# Connectors.net
KiCad netlist of a schematic drawn in Altium Designer
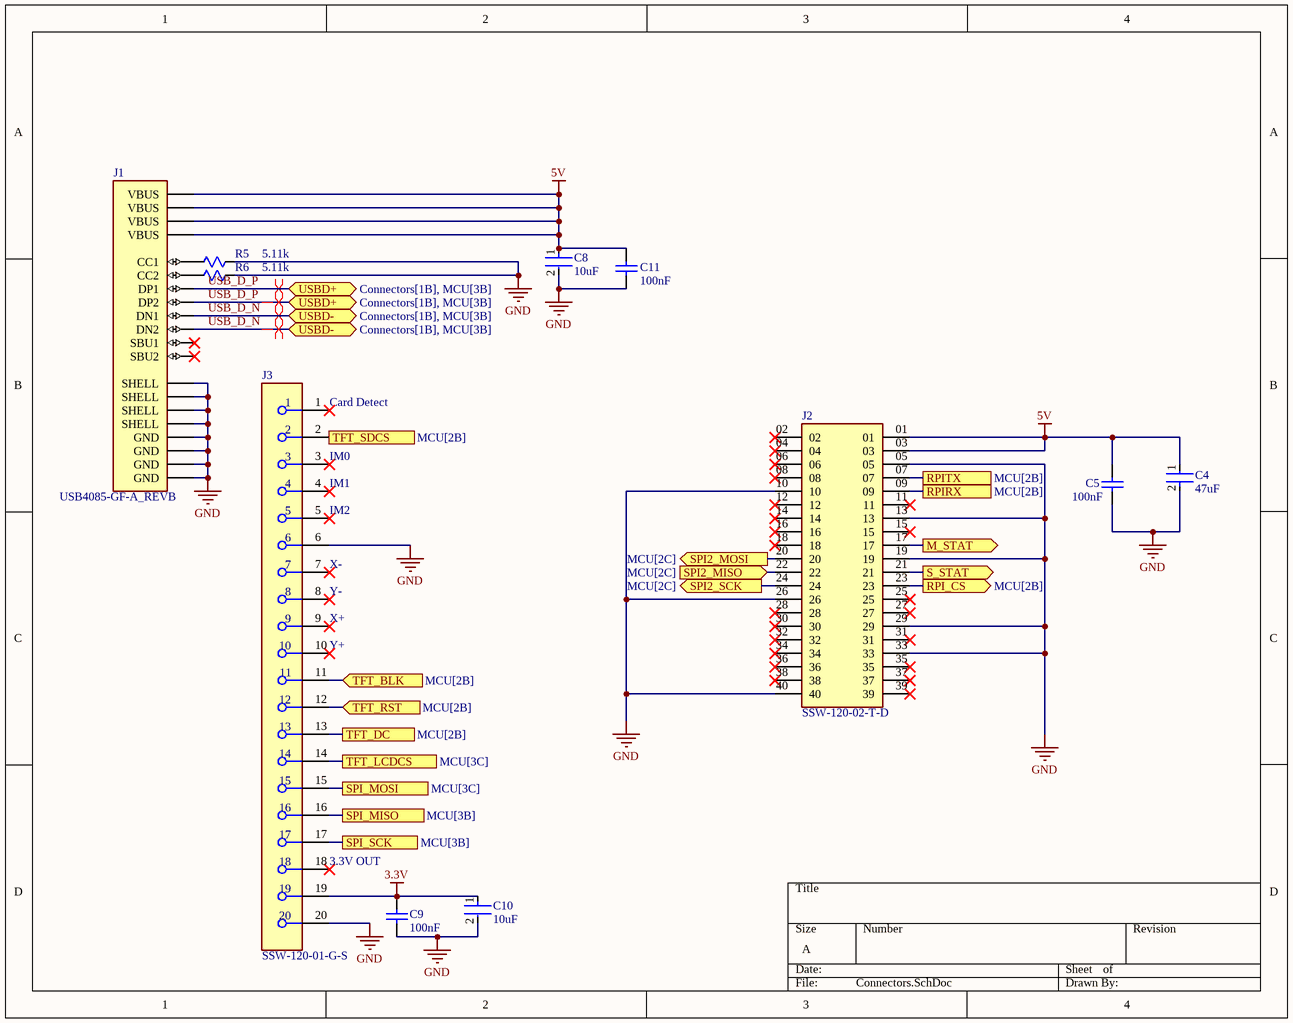
[diagram p0: Connectors.SchDoc]

(export (version "E")
  (design (tool "Eeschema 10.0.6"))
  (components
    (comp (ref "C4")
      (value "47uF")
      (footprint "FP-GRM31C-0_3-e0_3_0_8-IPC_C")
      (description "Chip Multilayer Ceramic Capacitors for General Purpose, 1206, 47uF, X5R, 15%, 20%, 16V")
      (fields (field (name "TOLERANCE") "20%"))
      (libsource (lib "Altium Content Vault") (part "f23184f103b6ebe33a8c269c53dcba6"))
    )
    (comp (ref "C5")
      (value "100nF")
      (footprint "CAPC1608X90X35LL10T15")
      (fields (field (name "PART NUMBER") "GRM188R71E104KA01D") (field (name "MANUFACTURER") "Murata"))
      (libsource (lib "Altium Content Vault") (part "CAP"))
    )
    (comp (ref "C8")
      (value "10uF")
      (footprint "FP-GRM21B-0_1-IPC_C")
      (description "Chip Multilayer Ceramic Capacitors for General Purpose, 0805, 10uF, X5R, 15%, 10%, 16V")
      (fields (field (name "TOLERANCE") "10%") (field (name "VOLTAGE") "16V"))
      (libsource (lib "Altium Content Vault") (part "b4654b650e69147ec39a6b967a45e02"))
    )
    (comp (ref "C9")
      (value "100nF")
      (footprint "CAPC1608X90X35LL10T15")
      (fields (field (name "PART NUMBER") "GRM188R71E104KA01D") (field (name "MANUFACTURER") "Murata"))
      (libsource (lib "Altium Content Vault") (part "CAP"))
    )
    (comp (ref "C10")
      (value "10uF")
      (footprint "FP-GRM21B-0_1-IPC_C")
      (description "Chip Multilayer Ceramic Capacitors for General Purpose, 0805, 10uF, X5R, 15%, 10%, 16V")
      (fields (field (name "TOLERANCE") "10%") (field (name "VOLTAGE") "16V"))
      (libsource (lib "Altium Content Vault") (part "b4654b650e69147ec39a6b967a45e02"))
    )
    (comp (ref "C11")
      (value "100nF")
      (footprint "CAPC1608X90X35LL10T15")
      (fields (field (name "PART NUMBER") "GRM188R71E104KA01D") (field (name "MANUFACTURER") "Murata"))
      (libsource (lib "Altium Content Vault") (part "CAP"))
    )
    (comp (ref "J1")
      (value "USB4085-GF-A_REVB")
      (footprint "GCT_USB4085-GF-A_REVB")
      (fields (field (name "MF") "Global Connector Technology") (field (name "MP") "USB4085-GF-A"))
      (libsource (lib "USB4085-GF-A_REVB") (part "USB4085-GF-A_REVB"))
    )
    (comp (ref "J2")
      (value "SSW-120-02-T-D")
      (footprint "SAMTEC_SSW-120-02-T-D")
      (description "40 Position Receptacle Connector 0.100 (2.54mm) Through Hole Tin")
      (fields (field (name "MF") "Samtec Inc."))
      (libsource (lib "SSW-120-02-T-D") (part "SSW-120-02-T-D"))
    )
    (comp (ref "J3")
      (value "SSW-120-01-G-S")
      (footprint "FP-SSW-120-01-G-S-MFG")
      (description "SSW-120-01-G-S SSW - Samtec 2.54mm Single Row Straight Socket Strip 8.5 Profile (mcv)(TO22)")
      (libsource (lib "Altium Content Vault") (part "dba14e038e6f7492952b7f1e871f183"))
    )
    (comp (ref "R5")
      (value "5.11k")
      (footprint "RESC1608X06N")
      (description "RES 5.11K OHM 1% 1/10W 0603")
      (fields (field (name "TOLERANCE") "0.01%") (field (name "PART NUMBER") "RES-0603-5K11-001"))
      (libsource (lib "Satellite Team") (part "RES-1"))
    )
    (comp (ref "R6")
      (value "5.11k")
      (footprint "RESC1608X06N")
      (description "RES 5.11K OHM 1% 1/10W 0603")
      (fields (field (name "TOLERANCE") "0.01%") (field (name "PART NUMBER") "RES-0603-5K11-001"))
      (libsource (lib "Satellite Team") (part "RES-1"))
    )
  )
  (nets
    (net (code "1") (name "/M_STAT") (class "Default")
      (node (ref "J2") (pin "17") (pinfunction "17_17") (pintype "passive"))
    )
    (net (code "2") (name "/RPIRX") (class "Default")
      (node (ref "J2") (pin "09") (pinfunction "09_09") (pintype "passive"))
    )
    (net (code "3") (name "/RPITX") (class "Default")
      (node (ref "J2") (pin "07") (pinfunction "07_07") (pintype "passive"))
    )
    (net (code "4") (name "/RPI_CS") (class "Default")
      (node (ref "J2") (pin "23") (pinfunction "23_23") (pintype "passive"))
    )
    (net (code "5") (name "/SPI2_MISO") (class "Default")
      (node (ref "J2") (pin "22") (pinfunction "22_22") (pintype "passive"))
    )
    (net (code "6") (name "/SPI2_MOSI") (class "Default")
      (node (ref "J2") (pin "20") (pinfunction "20_20") (pintype "passive"))
    )
    (net (code "7") (name "/SPI2_SCK") (class "Default")
      (node (ref "J2") (pin "24") (pinfunction "24_24") (pintype "passive"))
    )
    (net (code "8") (name "/SPI_MISO") (class "Default")
      (node (ref "J3") (pin "16") (pinfunction "16_16") (pintype "passive"))
    )
    (net (code "9") (name "/SPI_MOSI") (class "Default")
      (node (ref "J3") (pin "15") (pinfunction "15_15") (pintype "passive"))
    )
    (net (code "10") (name "/SPI_SCK") (class "Default")
      (node (ref "J3") (pin "17") (pinfunction "17_17") (pintype "passive"))
    )
    (net (code "11") (name "/S_STAT") (class "Default")
      (node (ref "J2") (pin "21") (pinfunction "21_21") (pintype "passive"))
    )
    (net (code "12") (name "/TFT_BLK") (class "Default")
      (node (ref "J3") (pin "11") (pinfunction "11_11") (pintype "passive"))
    )
    (net (code "13") (name "/TFT_DC") (class "Default")
      (node (ref "J3") (pin "13") (pinfunction "13_13") (pintype "passive"))
    )
    (net (code "14") (name "/TFT_LCDCS") (class "Default")
      (node (ref "J3") (pin "14") (pinfunction "14_14") (pintype "passive"))
    )
    (net (code "15") (name "/TFT_RST") (class "Default")
      (node (ref "J3") (pin "12") (pinfunction "12_12") (pintype "passive"))
    )
    (net (code "16") (name "/TFT_SDCS") (class "Default")
      (node (ref "J3") (pin "2") (pinfunction "2_2") (pintype "passive"))
    )
    (net (code "17") (name "/USB_D_N") (class "Default")
      (node (ref "J1") (pin "A7") (pinfunction "DN1_A7") (pintype "bidirectional"))
      (node (ref "J1") (pin "B7") (pinfunction "DN2_B7") (pintype "bidirectional"))
    )
    (net (code "18") (name "/USB_D_P") (class "Default")
      (node (ref "J1") (pin "A6") (pinfunction "DP1_A6") (pintype "bidirectional"))
      (node (ref "J1") (pin "B6") (pinfunction "DP2_B6") (pintype "bidirectional"))
    )
    (net (code "19") (name "3.3V") (class "Default")
      (node (ref "C10") (pin "1") (pinfunction "1_1") (pintype "passive"))
      (node (ref "C9") (pin "2") (pinfunction "2_2") (pintype "passive"))
      (node (ref "J3") (pin "19") (pinfunction "19_19") (pintype "passive"))
    )
    (net (code "20") (name "5V") (class "Default")
      (node (ref "C11") (pin "2") (pinfunction "2_2") (pintype "passive"))
      (node (ref "C4") (pin "1") (pinfunction "1_1") (pintype "passive"))
      (node (ref "C5") (pin "2") (pinfunction "2_2") (pintype "passive"))
      (node (ref "C8") (pin "1") (pinfunction "1_1") (pintype "passive"))
      (node (ref "J1") (pin "A4") (pinfunction "VBUS_A4") (pintype "power_in"))
      (node (ref "J1") (pin "A9") (pinfunction "VBUS_A9") (pintype "power_in"))
      (node (ref "J1") (pin "B4") (pinfunction "VBUS_B4") (pintype "power_in"))
      (node (ref "J1") (pin "B9") (pinfunction "VBUS_B9") (pintype "power_in"))
      (node (ref "J2") (pin "01") (pinfunction "01_01") (pintype "passive"))
      (node (ref "J2") (pin "03") (pinfunction "03_03") (pintype "passive"))
    )
    (net (code "21") (name "GND") (class "Default")
      (node (ref "C10") (pin "2") (pinfunction "2_2") (pintype "passive"))
      (node (ref "C11") (pin "1") (pinfunction "1_1") (pintype "passive"))
      (node (ref "C4") (pin "2") (pinfunction "2_2") (pintype "passive"))
      (node (ref "C5") (pin "1") (pinfunction "1_1") (pintype "passive"))
      (node (ref "C8") (pin "2") (pinfunction "2_2") (pintype "passive"))
      (node (ref "C9") (pin "1") (pinfunction "1_1") (pintype "passive"))
      (node (ref "J1") (pin "A1") (pinfunction "GND_A1") (pintype "power_in"))
      (node (ref "J1") (pin "A12") (pinfunction "GND_A12") (pintype "power_in"))
      (node (ref "J1") (pin "B1") (pinfunction "GND_B1") (pintype "power_in"))
      (node (ref "J1") (pin "B12") (pinfunction "GND_B12") (pintype "power_in"))
      (node (ref "J1") (pin "S1") (pinfunction "SHELL_S1") (pintype "passive"))
      (node (ref "J1") (pin "S2") (pinfunction "SHELL_S2") (pintype "passive"))
      (node (ref "J1") (pin "S3") (pinfunction "SHELL_S3") (pintype "passive"))
      (node (ref "J1") (pin "S4") (pinfunction "SHELL_S4") (pintype "passive"))
      (node (ref "J2") (pin "05") (pinfunction "05_05") (pintype "passive"))
      (node (ref "J2") (pin "10") (pinfunction "10_10") (pintype "passive"))
      (node (ref "J2") (pin "13") (pinfunction "13_13") (pintype "passive"))
      (node (ref "J2") (pin "19") (pinfunction "19_19") (pintype "passive"))
      (node (ref "J2") (pin "26") (pinfunction "26_26") (pintype "passive"))
      (node (ref "J2") (pin "29") (pinfunction "29_29") (pintype "passive"))
      (node (ref "J2") (pin "33") (pinfunction "33_33") (pintype "passive"))
      (node (ref "J2") (pin "40") (pinfunction "40_40") (pintype "passive"))
      (node (ref "J3") (pin "20") (pinfunction "20_20") (pintype "passive"))
      (node (ref "J3") (pin "6") (pinfunction "6_6") (pintype "passive"))
      (node (ref "R5") (pin "2") (pinfunction "2_2") (pintype "passive"))
      (node (ref "R6") (pin "2") (pinfunction "2_2") (pintype "passive"))
    )
    (net (code "22") (name "Net-(J1-CC1)") (class "Default")
      (node (ref "J1") (pin "A5") (pinfunction "CC1_A5") (pintype "bidirectional"))
      (node (ref "R5") (pin "1") (pinfunction "1_1") (pintype "passive"))
    )
    (net (code "23") (name "Net-(J1-CC2)") (class "Default")
      (node (ref "J1") (pin "B5") (pinfunction "CC2_B5") (pintype "bidirectional"))
      (node (ref "R6") (pin "1") (pinfunction "1_1") (pintype "passive"))
    )
    (net (code "24") (name "unconnected-(J1-SBU1-PadA8)") (class "Default")
      (node (ref "J1") (pin "A8") (pinfunction "SBU1_A8") (pintype "bidirectional+no_connect"))
    )
    (net (code "25") (name "unconnected-(J1-SBU2-PadB8)") (class "Default")
      (node (ref "J1") (pin "B8") (pinfunction "SBU2_B8") (pintype "bidirectional+no_connect"))
    )
    (net (code "26") (name "unconnected-(J2-Pad02)") (class "Default")
      (node (ref "J2") (pin "02") (pinfunction "02_02") (pintype "passive+no_connect"))
    )
    (net (code "27") (name "unconnected-(J2-Pad04)") (class "Default")
      (node (ref "J2") (pin "04") (pinfunction "04_04") (pintype "passive+no_connect"))
    )
    (net (code "28") (name "unconnected-(J2-Pad06)") (class "Default")
      (node (ref "J2") (pin "06") (pinfunction "06_06") (pintype "passive+no_connect"))
    )
    (net (code "29") (name "unconnected-(J2-Pad08)") (class "Default")
      (node (ref "J2") (pin "08") (pinfunction "08_08") (pintype "passive+no_connect"))
    )
    (net (code "30") (name "unconnected-(J2-Pad11)") (class "Default")
      (node (ref "J2") (pin "11") (pinfunction "11_11") (pintype "passive+no_connect"))
    )
    (net (code "31") (name "unconnected-(J2-Pad12)") (class "Default")
      (node (ref "J2") (pin "12") (pinfunction "12_12") (pintype "passive+no_connect"))
    )
    (net (code "32") (name "unconnected-(J2-Pad14)") (class "Default")
      (node (ref "J2") (pin "14") (pinfunction "14_14") (pintype "passive+no_connect"))
    )
    (net (code "33") (name "unconnected-(J2-Pad15)") (class "Default")
      (node (ref "J2") (pin "15") (pinfunction "15_15") (pintype "passive+no_connect"))
    )
    (net (code "34") (name "unconnected-(J2-Pad16)") (class "Default")
      (node (ref "J2") (pin "16") (pinfunction "16_16") (pintype "passive+no_connect"))
    )
    (net (code "35") (name "unconnected-(J2-Pad18)") (class "Default")
      (node (ref "J2") (pin "18") (pinfunction "18_18") (pintype "passive+no_connect"))
    )
    (net (code "36") (name "unconnected-(J2-Pad25)") (class "Default")
      (node (ref "J2") (pin "25") (pinfunction "25_25") (pintype "passive+no_connect"))
    )
    (net (code "37") (name "unconnected-(J2-Pad27)") (class "Default")
      (node (ref "J2") (pin "27") (pinfunction "27_27") (pintype "passive+no_connect"))
    )
    (net (code "38") (name "unconnected-(J2-Pad28)") (class "Default")
      (node (ref "J2") (pin "28") (pinfunction "28_28") (pintype "passive+no_connect"))
    )
    (net (code "39") (name "unconnected-(J2-Pad30)") (class "Default")
      (node (ref "J2") (pin "30") (pinfunction "30_30") (pintype "passive+no_connect"))
    )
    (net (code "40") (name "unconnected-(J2-Pad31)") (class "Default")
      (node (ref "J2") (pin "31") (pinfunction "31_31") (pintype "passive+no_connect"))
    )
    (net (code "41") (name "unconnected-(J2-Pad32)") (class "Default")
      (node (ref "J2") (pin "32") (pinfunction "32_32") (pintype "passive+no_connect"))
    )
    (net (code "42") (name "unconnected-(J2-Pad34)") (class "Default")
      (node (ref "J2") (pin "34") (pinfunction "34_34") (pintype "passive+no_connect"))
    )
    (net (code "43") (name "unconnected-(J2-Pad35)") (class "Default")
      (node (ref "J2") (pin "35") (pinfunction "35_35") (pintype "passive+no_connect"))
    )
    (net (code "44") (name "unconnected-(J2-Pad36)") (class "Default")
      (node (ref "J2") (pin "36") (pinfunction "36_36") (pintype "passive+no_connect"))
    )
    (net (code "45") (name "unconnected-(J2-Pad37)") (class "Default")
      (node (ref "J2") (pin "37") (pinfunction "37_37") (pintype "passive+no_connect"))
    )
    (net (code "46") (name "unconnected-(J2-Pad38)") (class "Default")
      (node (ref "J2") (pin "38") (pinfunction "38_38") (pintype "passive+no_connect"))
    )
    (net (code "47") (name "unconnected-(J2-Pad39)") (class "Default")
      (node (ref "J2") (pin "39") (pinfunction "39_39") (pintype "passive+no_connect"))
    )
    (net (code "48") (name "unconnected-(J3-Pad1)") (class "Default")
      (node (ref "J3") (pin "1") (pinfunction "1_1") (pintype "passive+no_connect"))
    )
    (net (code "49") (name "unconnected-(J3-Pad3)") (class "Default")
      (node (ref "J3") (pin "3") (pinfunction "3_3") (pintype "passive+no_connect"))
    )
    (net (code "50") (name "unconnected-(J3-Pad4)") (class "Default")
      (node (ref "J3") (pin "4") (pinfunction "4_4") (pintype "passive+no_connect"))
    )
    (net (code "51") (name "unconnected-(J3-Pad5)") (class "Default")
      (node (ref "J3") (pin "5") (pinfunction "5_5") (pintype "passive+no_connect"))
    )
    (net (code "52") (name "unconnected-(J3-Pad7)") (class "Default")
      (node (ref "J3") (pin "7") (pinfunction "7_7") (pintype "passive+no_connect"))
    )
    (net (code "53") (name "unconnected-(J3-Pad8)") (class "Default")
      (node (ref "J3") (pin "8") (pinfunction "8_8") (pintype "passive+no_connect"))
    )
    (net (code "54") (name "unconnected-(J3-Pad9)") (class "Default")
      (node (ref "J3") (pin "9") (pinfunction "9_9") (pintype "passive+no_connect"))
    )
    (net (code "55") (name "unconnected-(J3-Pad10)") (class "Default")
      (node (ref "J3") (pin "10") (pinfunction "10_10") (pintype "passive+no_connect"))
    )
    (net (code "56") (name "unconnected-(J3-Pad18)") (class "Default")
      (node (ref "J3") (pin "18") (pinfunction "18_18") (pintype "passive+no_connect"))
    )
  )
)
